# samd21_actuatorhub_Lite_TQFP32_1_0_feb20.net
KiCad netlist of a schematic drawn in EAGLE
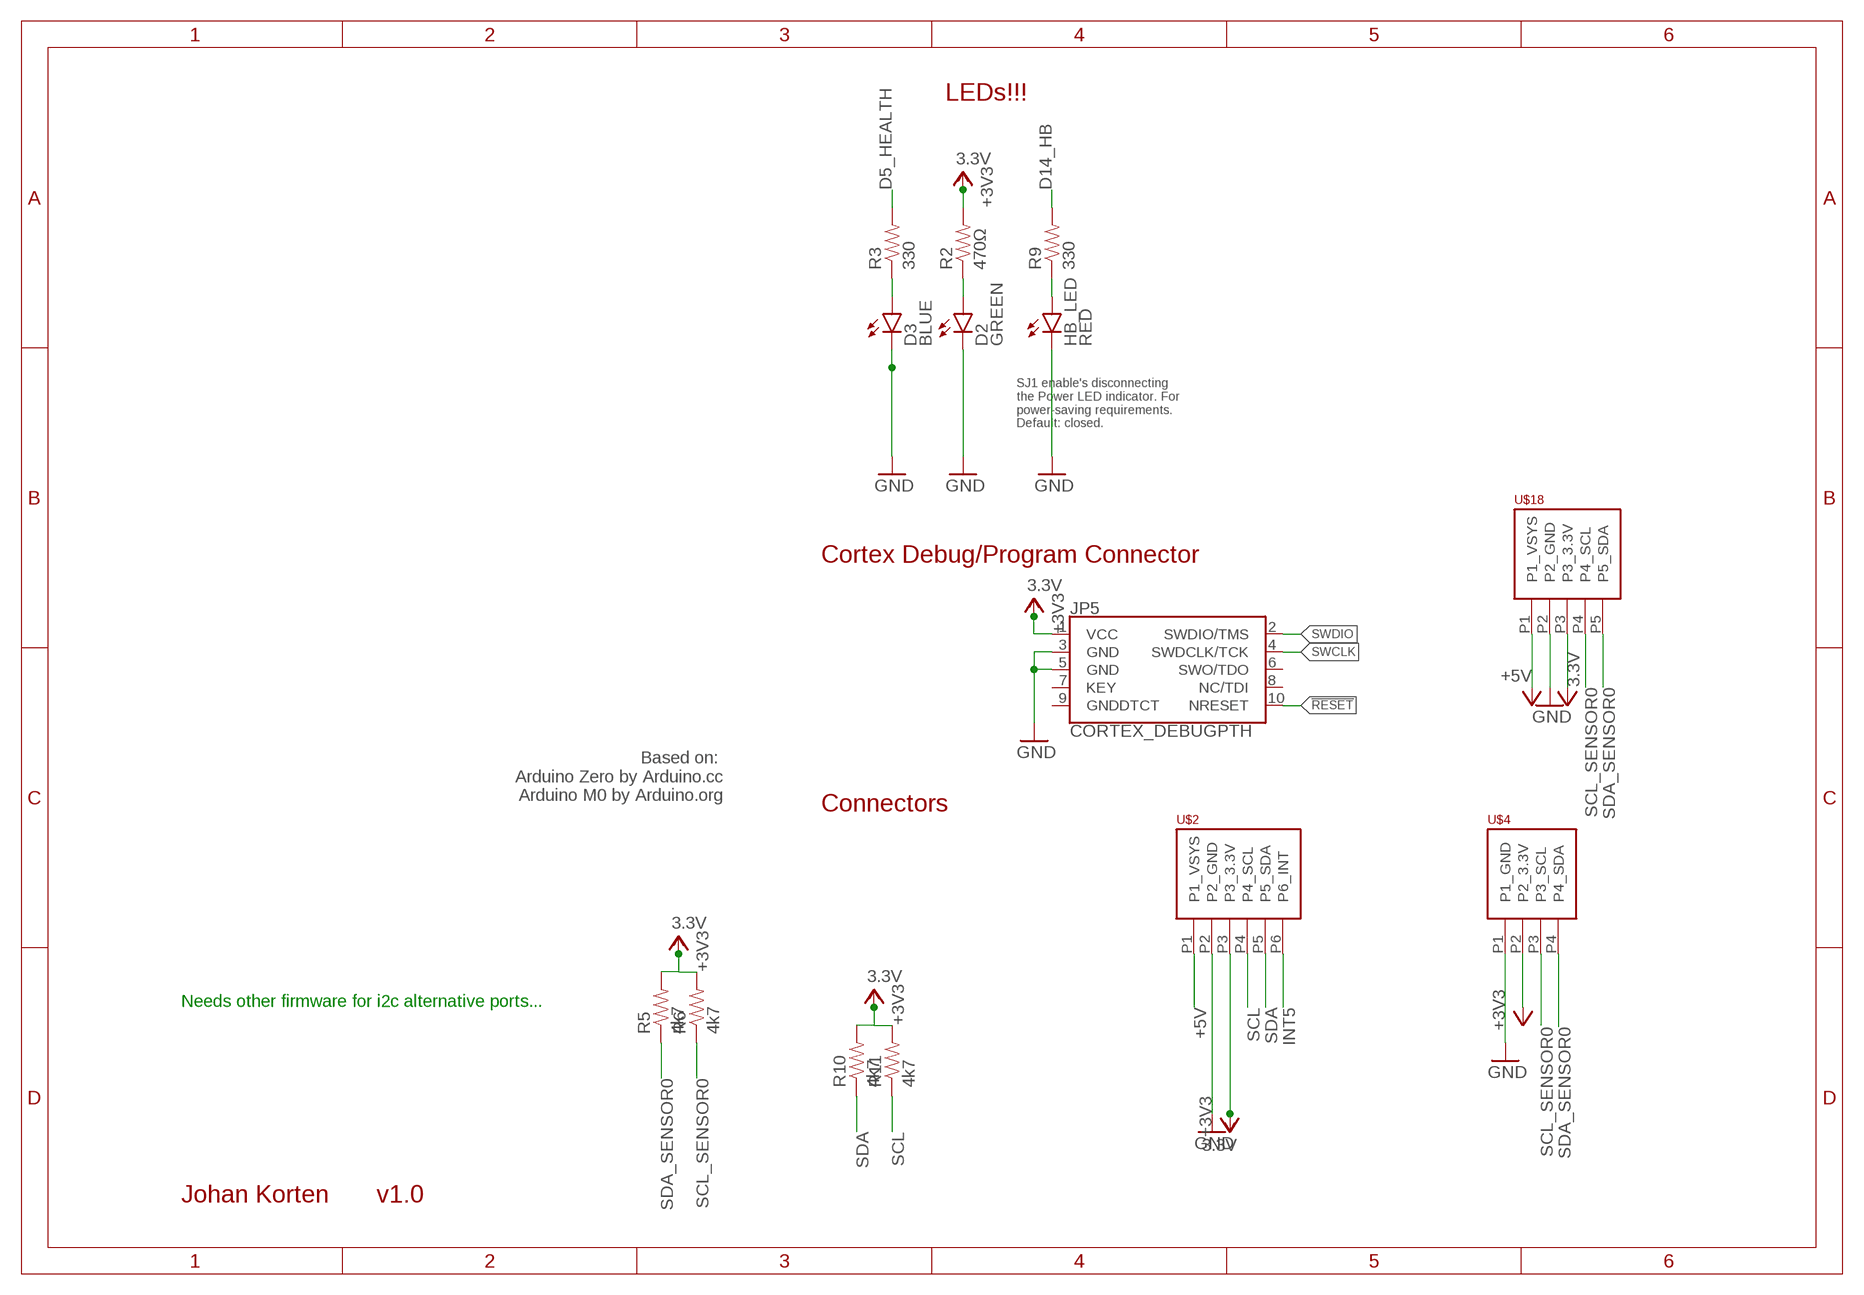
[diagram p0: schematic, sheet 1]
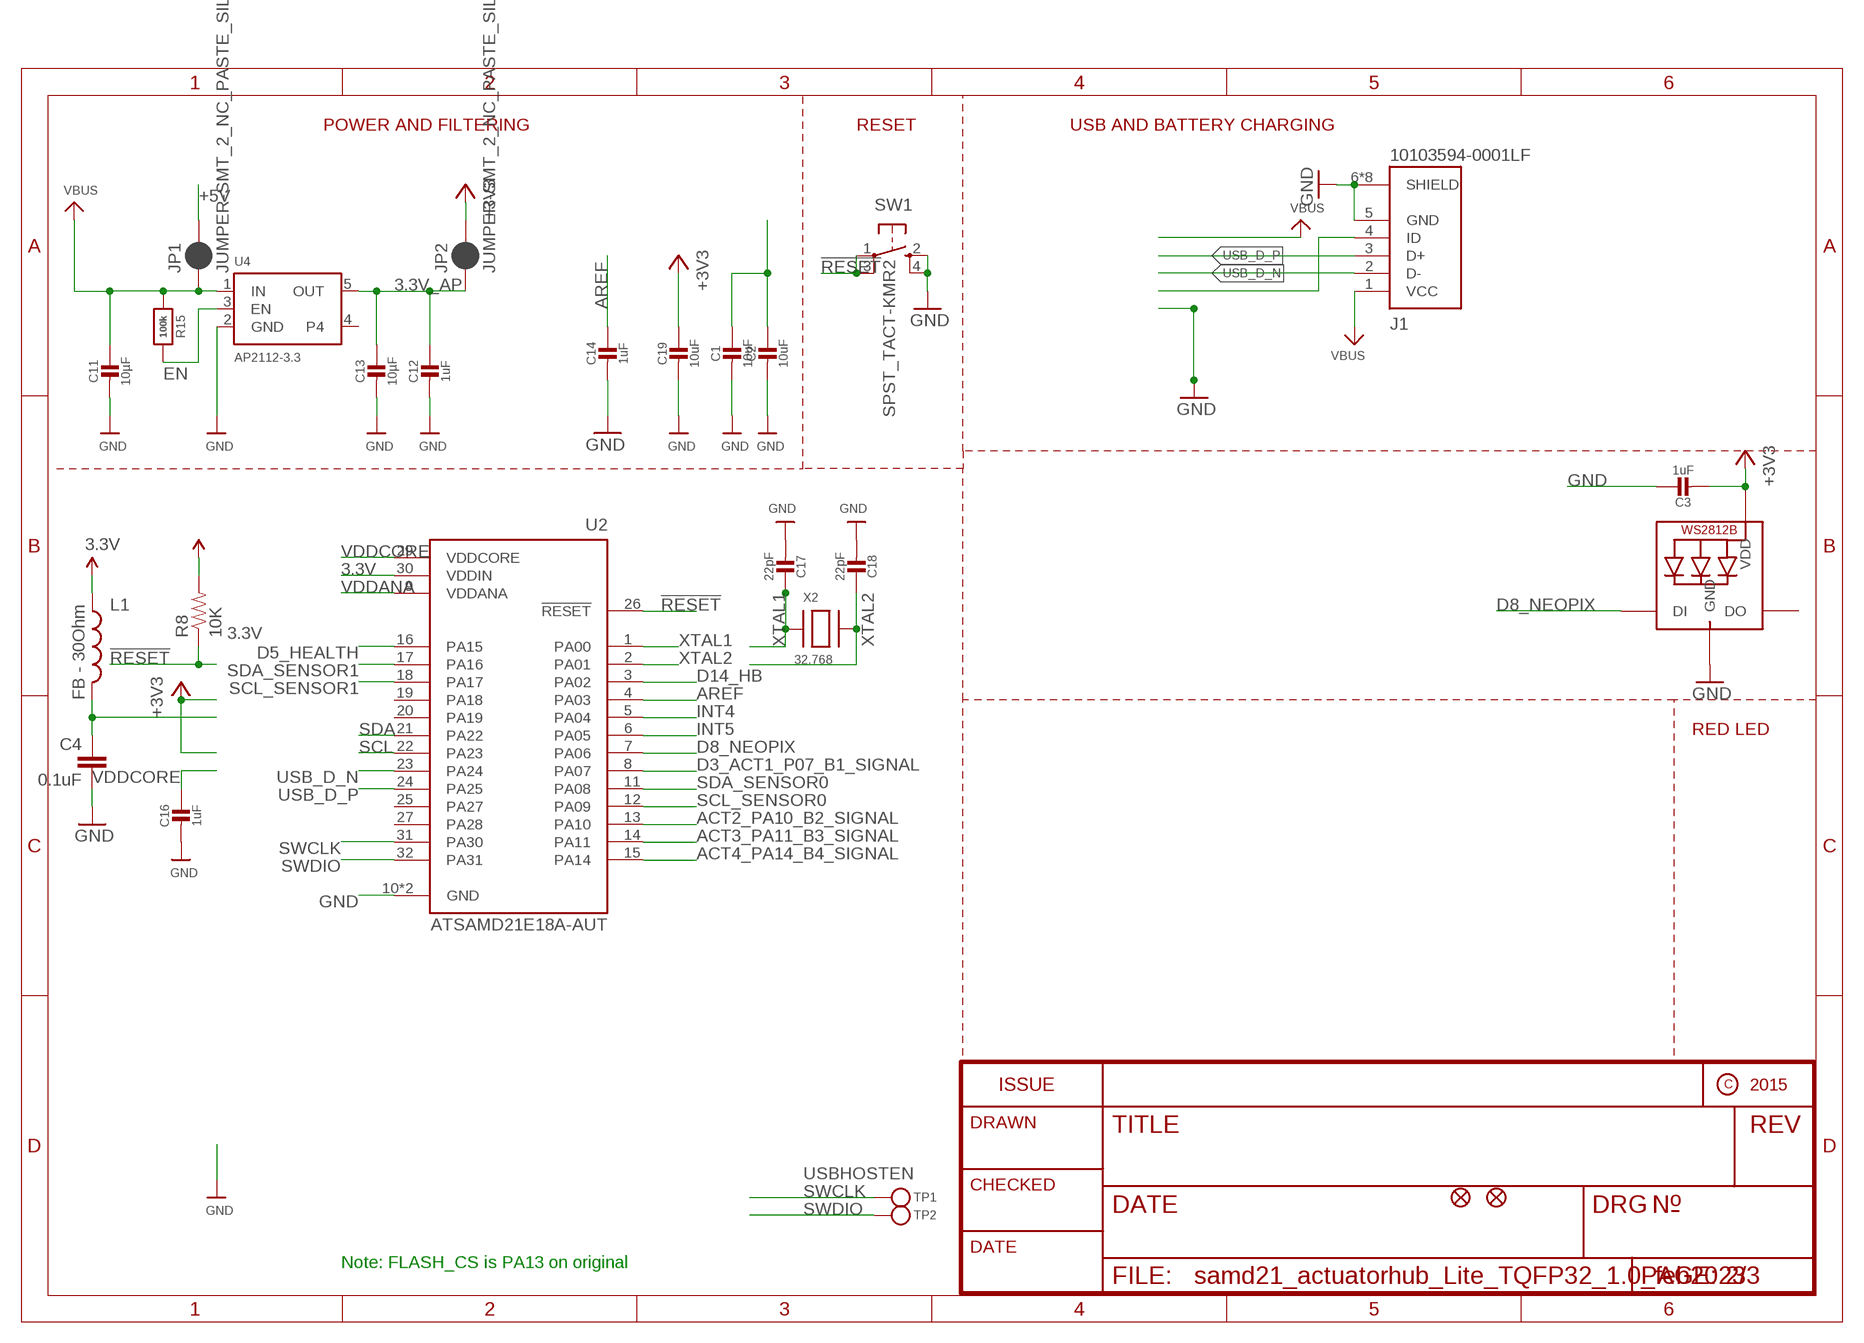
[diagram p1: schematic, sheet 2]
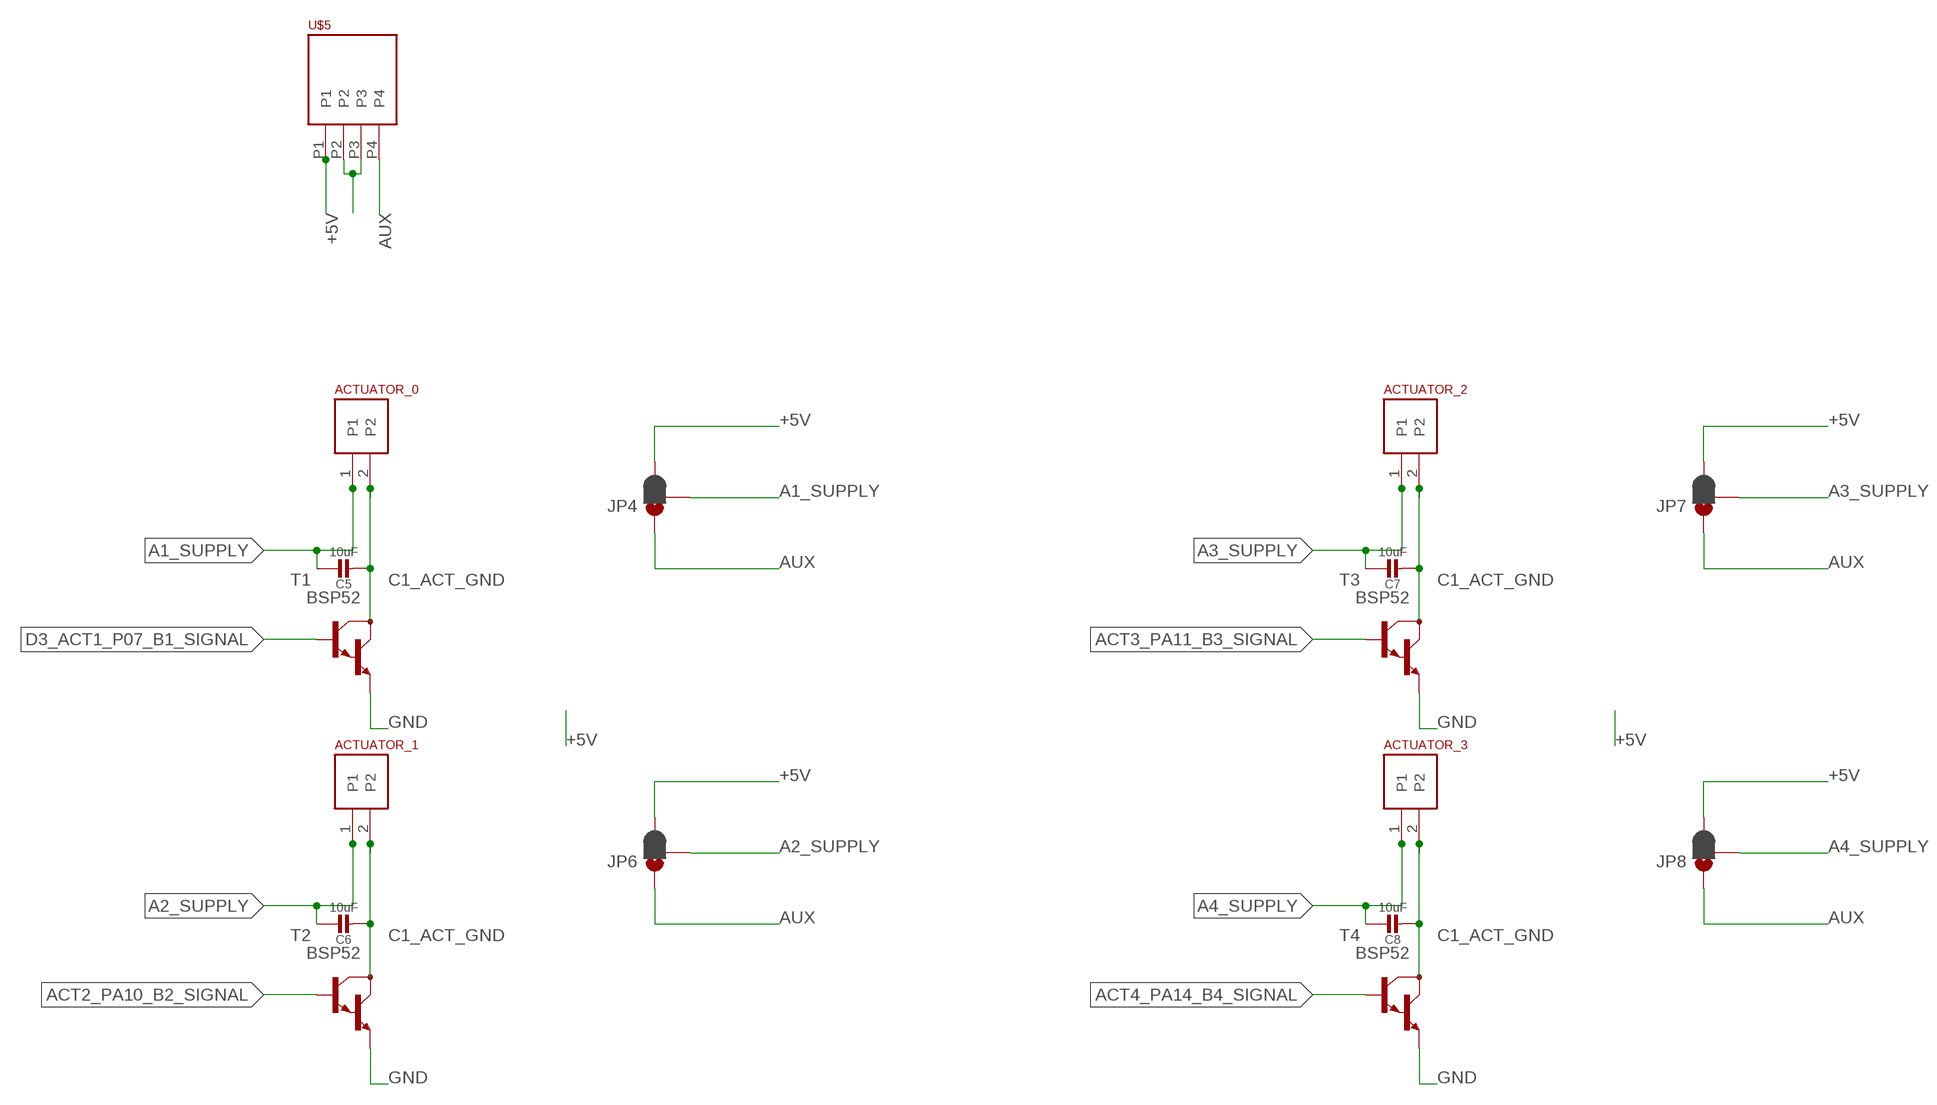
[diagram p2: schematic, sheet 3]

(export (version "E")
  (design (tool "Eeschema 10.0.6"))
  (components
    (comp (ref "ACTUATOR_0")
      (value "PHOENIX_PTSM_M2TH")
      (footprint "eagle-import:PTSM_M2_THRHOLE")
      (libsource (lib "eagle-import") (part "PHOENIX_PTSM_M2TH"))
    )
    (comp (ref "ACTUATOR_1")
      (value "PHOENIX_PTSM_M2TH")
      (footprint "eagle-import:PTSM_M2_THRHOLE")
      (libsource (lib "eagle-import") (part "PHOENIX_PTSM_M2TH"))
    )
    (comp (ref "ACTUATOR_2")
      (value "PHOENIX_PTSM_M2TH")
      (footprint "eagle-import:PTSM_M2_THRHOLE")
      (libsource (lib "eagle-import") (part "PHOENIX_PTSM_M2TH"))
    )
    (comp (ref "ACTUATOR_3")
      (value "PHOENIX_PTSM_M2TH")
      (footprint "eagle-import:PTSM_M2_THRHOLE")
      (libsource (lib "eagle-import") (part "PHOENIX_PTSM_M2TH"))
    )
    (comp (ref "C5")
      (value "10uF")
      (footprint "eagle-import:0805-NO")
      (libsource (lib "eagle-import") (part "CAP_CERAMIC0805-NOOUTLINE"))
    )
    (comp (ref "C6")
      (value "10uF")
      (footprint "eagle-import:0805-NO")
      (libsource (lib "eagle-import") (part "CAP_CERAMIC0805-NOOUTLINE"))
    )
    (comp (ref "C7")
      (value "10uF")
      (footprint "eagle-import:0805-NO")
      (libsource (lib "eagle-import") (part "CAP_CERAMIC0805-NOOUTLINE"))
    )
    (comp (ref "C8")
      (value "10uF")
      (footprint "eagle-import:0805-NO")
      (libsource (lib "eagle-import") (part "CAP_CERAMIC0805-NOOUTLINE"))
    )
    (comp (ref "JP4")
      (value "JUMPER-SMT_3_1-NC_PASTE_SILK")
      (footprint "eagle-import:SMT-JUMPER_3_1-NC_PASTE_SILK")
      (libsource (lib "eagle-import") (part "JUMPER-SMT_3_1-NC_PASTE_SILK"))
    )
    (comp (ref "JP6")
      (value "JUMPER-SMT_3_1-NC_PASTE_SILK")
      (footprint "eagle-import:SMT-JUMPER_3_1-NC_PASTE_SILK")
      (libsource (lib "eagle-import") (part "JUMPER-SMT_3_1-NC_PASTE_SILK"))
    )
    (comp (ref "JP7")
      (value "JUMPER-SMT_3_1-NC_PASTE_SILK")
      (footprint "eagle-import:SMT-JUMPER_3_1-NC_PASTE_SILK")
      (libsource (lib "eagle-import") (part "JUMPER-SMT_3_1-NC_PASTE_SILK"))
    )
    (comp (ref "JP8")
      (value "JUMPER-SMT_3_1-NC_PASTE_SILK")
      (footprint "eagle-import:SMT-JUMPER_3_1-NC_PASTE_SILK")
      (libsource (lib "eagle-import") (part "JUMPER-SMT_3_1-NC_PASTE_SILK"))
    )
    (comp (ref "T1")
      (value "BSP52")
      (footprint "eagle-import:SOT-223-4")
      (fields (field (name "MF") "ON Semiconductor"))
      (libsource (lib "eagle-import") (part "BSP52"))
    )
    (comp (ref "T2")
      (value "BSP52")
      (footprint "eagle-import:SOT-223-4")
      (fields (field (name "MF") "ON Semiconductor"))
      (libsource (lib "eagle-import") (part "BSP52"))
    )
    (comp (ref "T3")
      (value "BSP52")
      (footprint "eagle-import:SOT-223-4")
      (fields (field (name "MF") "ON Semiconductor"))
      (libsource (lib "eagle-import") (part "BSP52"))
    )
    (comp (ref "T4")
      (value "BSP52")
      (footprint "eagle-import:SOT-223-4")
      (fields (field (name "MF") "ON Semiconductor"))
      (libsource (lib "eagle-import") (part "BSP52"))
    )
    (comp (ref "U$5")
      (value "PHOENIX_PTSM_M4_TH_ANGLE")
      (footprint "eagle-import:PTSM_M4_TH_ANGLE_NEUTRAL")
      (libsource (lib "eagle-import") (part "PHOENIX_PTSM_M4_TH_ANGLE"))
    )
    (comp (ref "C1")
      (value "10uF")
      (footprint "eagle-import:0805-NO")
      (libsource (lib "eagle-import") (part "CAP_CERAMIC0805-NOOUTLINE"))
    )
    (comp (ref "C2")
      (value "10uF")
      (footprint "eagle-import:0805-NO")
      (libsource (lib "eagle-import") (part "CAP_CERAMIC0805-NOOUTLINE"))
    )
    (comp (ref "C3")
      (value "1uF")
      (footprint "eagle-import:0603-NO")
      (libsource (lib "eagle-import") (part "CAP_CERAMIC0603_NO"))
    )
    (comp (ref "C4")
      (value "0.1uF")
      (footprint "eagle-import:0402-CAP")
      (libsource (lib "eagle-import") (part "0.1UF-16V(+-10%)(0402)"))
    )
    (comp (ref "C11")
      (value "10µF")
      (footprint "eagle-import:0805-NO")
      (libsource (lib "eagle-import") (part "CAP_CERAMIC0805-NOOUTLINE"))
    )
    (comp (ref "C12")
      (value "1uF")
      (footprint "eagle-import:0603-NO")
      (libsource (lib "eagle-import") (part "CAP_CERAMIC0603_NO"))
    )
    (comp (ref "C13")
      (value "10µF")
      (footprint "eagle-import:0805-NO")
      (libsource (lib "eagle-import") (part "CAP_CERAMIC0805-NOOUTLINE"))
    )
    (comp (ref "C14")
      (value "1uF")
      (footprint "eagle-import:0603-NO")
      (libsource (lib "eagle-import") (part "CAP_CERAMIC0603_NO"))
    )
    (comp (ref "C16")
      (value "1uF")
      (footprint "eagle-import:0603-NO")
      (libsource (lib "eagle-import") (part "CAP_CERAMIC0603_NO"))
    )
    (comp (ref "C17")
      (value "22pF")
      (footprint "eagle-import:0603-NO")
      (libsource (lib "eagle-import") (part "CAP_CERAMIC0603_NO"))
    )
    (comp (ref "C18")
      (value "22pF")
      (footprint "eagle-import:0603-NO")
      (libsource (lib "eagle-import") (part "CAP_CERAMIC0603_NO"))
    )
    (comp (ref "C19")
      (value "10uF")
      (footprint "eagle-import:0805-NO")
      (libsource (lib "eagle-import") (part "CAP_CERAMIC0805-NOOUTLINE"))
    )
    (comp (ref "J1")
      (value "10103594-0001LF")
      (footprint "eagle-import:AMPHENOL_10103594-0001LF")
      (fields (field (name "MF") "AMPHENOL ICC / FCI"))
      (libsource (lib "eagle-import") (part "10103594-0001LF"))
    )
    (comp (ref "JP1")
      (value "JUMPER-SMT_2_NC_PASTE_SILK")
      (footprint "eagle-import:SMT-JUMPER_2_NC_PASTE_SILK")
      (libsource (lib "eagle-import") (part "JUMPER-SMT_2_NC_PASTE_SILK"))
    )
    (comp (ref "JP2")
      (value "JUMPER-SMT_2_NC_PASTE_SILK")
      (footprint "eagle-import:SMT-JUMPER_2_NC_PASTE_SILK")
      (libsource (lib "eagle-import") (part "JUMPER-SMT_2_NC_PASTE_SILK"))
    )
    (comp (ref "L1")
      (value "FB - 30Ohm")
      (footprint "eagle-import:0603")
      (libsource (lib "eagle-import") (part "INDUCTOR0603"))
    )
    (comp (ref "LED1")
      (value "WS2812B3535")
      (footprint "eagle-import:LED3535")
      (libsource (lib "eagle-import") (part "WS2812B3535"))
    )
    (comp (ref "R8")
      (value "10K")
      (footprint "eagle-import:0603-RES")
      (libsource (lib "eagle-import") (part "10KOHM-1/10W-1%(0603)0603"))
    )
    (comp (ref "R15")
      (value "100k")
      (footprint "eagle-import:0603-NO")
      (libsource (lib "eagle-import") (part "RESISTOR_0603_NOOUT"))
    )
    (comp (ref "SW1")
      (value "SPST_TACT-KMR2")
      (footprint "eagle-import:KMR2")
      (libsource (lib "eagle-import") (part "SPST_TACT-KMR2"))
    )
    (comp (ref "TP1")
      (value "TESTPOINTROUND1.5MM")
      (footprint "eagle-import:TESTPOINT_ROUND_1.5MM")
      (libsource (lib "eagle-import") (part "TESTPOINTROUND1.5MM"))
    )
    (comp (ref "TP2")
      (value "TESTPOINTROUND1.5MM")
      (footprint "eagle-import:TESTPOINT_ROUND_1.5MM")
      (libsource (lib "eagle-import") (part "TESTPOINTROUND1.5MM"))
    )
    (comp (ref "U$34")
      (value "FIDUCIAL\"\"")
      (footprint "eagle-import:FIDUCIAL_1MM")
      (libsource (lib "eagle-import") (part "FIDUCIAL{dblquote}{dblquote}"))
    )
    (comp (ref "U$35")
      (value "FIDUCIAL\"\"")
      (footprint "eagle-import:FIDUCIAL_1MM")
      (libsource (lib "eagle-import") (part "FIDUCIAL{dblquote}{dblquote}"))
    )
    (comp (ref "U2")
      (value "ATSAMD21E18A-AUT")
      (footprint "eagle-import:QFP80P900X900X120-32N")
      (fields (field (name "MF") "Microchip") (field (name "MP") "ATSAMD21E18A-AU"))
      (libsource (lib "eagle-import") (part "ATSAMD21E18A-AUT"))
    )
    (comp (ref "U4")
      (value "AP2112-3.3")
      (footprint "eagle-import:SOT23-5")
      (libsource (lib "eagle-import") (part "VREG_SOT23-5"))
    )
    (comp (ref "X2")
      (value "32.768")
      (footprint "eagle-import:XTAL3215")
      (libsource (lib "eagle-import") (part "XTAL-3.2X1.5"))
    )
    (comp (ref "D2")
      (value "GREEN")
      (footprint "eagle-import:LED-0603")
      (libsource (lib "eagle-import") (part "LED-RED0603"))
    )
    (comp (ref "D3")
      (value "BLUE")
      (footprint "eagle-import:LED-0603")
      (libsource (lib "eagle-import") (part "LED-BLUE0603"))
    )
    (comp (ref "HB_LED")
      (value "RED")
      (footprint "eagle-import:LED-0603")
      (libsource (lib "eagle-import") (part "LED-RED0603"))
    )
    (comp (ref "JP5")
      (value "CORTEX_DEBUGPTH")
      (footprint "eagle-import:2X5-PTH-1.27MM")
      (libsource (lib "eagle-import") (part "CORTEX_DEBUGPTH"))
    )
    (comp (ref "R2")
      (value "470Ω")
      (footprint "eagle-import:0603-RES")
      (libsource (lib "eagle-import") (part "330OHM1/10W1%(0603)"))
    )
    (comp (ref "R3")
      (value "330")
      (footprint "eagle-import:0603-RES")
      (libsource (lib "eagle-import") (part "330OHM1/10W1%(0603)"))
    )
    (comp (ref "R5")
      (value "4k7")
      (footprint "eagle-import:0603-RES")
      (libsource (lib "eagle-import") (part "330OHM1/10W1%(0603)"))
    )
    (comp (ref "R6")
      (value "4k7")
      (footprint "eagle-import:0603-RES")
      (libsource (lib "eagle-import") (part "330OHM1/10W1%(0603)"))
    )
    (comp (ref "R9")
      (value "330")
      (footprint "eagle-import:0603-RES")
      (libsource (lib "eagle-import") (part "330OHM1/10W1%(0603)"))
    )
    (comp (ref "R10")
      (value "4k7")
      (footprint "eagle-import:0603-RES")
      (libsource (lib "eagle-import") (part "330OHM1/10W1%(0603)"))
    )
    (comp (ref "R11")
      (value "4k7")
      (footprint "eagle-import:0603-RES")
      (libsource (lib "eagle-import") (part "330OHM1/10W1%(0603)"))
    )
    (comp (ref "U$2")
      (value "PHOENIX_PTSM_M6_TH_I2CPPANGLE")
      (footprint "eagle-import:PTSM_M6_THRHOLE")
      (libsource (lib "eagle-import") (part "PHOENIX_PTSM_M6_TH_I2CPPANGLE"))
    )
    (comp (ref "U$4")
      (value "PHOENIX_PTSM_M4_THANGLE")
      (footprint "eagle-import:PTSM_M4_TH")
      (libsource (lib "eagle-import") (part "PHOENIX_PTSM_M4_THANGLE"))
    )
    (comp (ref "U$18")
      (value "PHOENIX_PTSM_M5_TH_I2C++")
      (footprint "eagle-import:PTSM_M5_THRHOLE")
      (libsource (lib "eagle-import") (part "PHOENIX_PTSM_M5_TH_I2C++"))
    )
  )
  (nets
    (net (code "1") (name "+5V") (class "Default")
      (node (ref "C1") (pin "1") (pinfunction "1_1") (pintype "passive"))
      (node (ref "C2") (pin "1") (pinfunction "1_1") (pintype "passive"))
      (node (ref "JP1") (pin "2") (pinfunction "2_2") (pintype "passive"))
      (node (ref "JP4") (pin "3") (pinfunction "3_3") (pintype "passive"))
      (node (ref "JP6") (pin "3") (pinfunction "3_3") (pintype "passive"))
      (node (ref "JP7") (pin "3") (pinfunction "3_3") (pintype "passive"))
      (node (ref "JP8") (pin "3") (pinfunction "3_3") (pintype "passive"))
      (node (ref "U$18") (pin "P1") (pinfunction "P1_VSYS_P1") (pintype "power_in"))
      (node (ref "U$2") (pin "P1") (pinfunction "P1_VSYS_P1") (pintype "power_in"))
      (node (ref "U$5") (pin "P1") (pinfunction "P1_P1") (pintype "power_in"))
    )
    (net (code "2") (name "3.3V") (class "Default")
      (node (ref "C19") (pin "1") (pinfunction "1_1") (pintype "passive"))
      (node (ref "C3") (pin "2") (pinfunction "2_2") (pintype "passive"))
      (node (ref "JP2") (pin "2") (pinfunction "2_2") (pintype "passive"))
      (node (ref "JP5") (pin "1") (pinfunction "VCC_1") (pintype "bidirectional"))
      (node (ref "L1") (pin "1") (pinfunction "1_1") (pintype "passive"))
      (node (ref "LED1") (pin "2") (pinfunction "VDD_2") (pintype "power_in"))
      (node (ref "R10") (pin "2") (pinfunction "2_2") (pintype "passive"))
      (node (ref "R11") (pin "2") (pinfunction "2_2") (pintype "passive"))
      (node (ref "R2") (pin "2") (pinfunction "2_2") (pintype "passive"))
      (node (ref "R5") (pin "2") (pinfunction "2_2") (pintype "passive"))
      (node (ref "R6") (pin "2") (pinfunction "2_2") (pintype "passive"))
      (node (ref "R8") (pin "2") (pinfunction "2_2") (pintype "passive"))
      (node (ref "U$18") (pin "P3") (pinfunction "P3_3.3V_P3") (pintype "power_in"))
      (node (ref "U$2") (pin "P3") (pinfunction "P3_3.3V_P3") (pintype "power_in"))
      (node (ref "U$4") (pin "P2") (pinfunction "P2_3.3V_P2") (pintype "power_in"))
      (node (ref "U2") (pin "30") (pinfunction "VDDIN_30") (pintype "power_in"))
    )
    (net (code "3") (name "3.3V_AP") (class "Default")
      (node (ref "C12") (pin "1") (pinfunction "1_1") (pintype "passive"))
      (node (ref "C13") (pin "1") (pinfunction "1_1") (pintype "passive"))
      (node (ref "JP2") (pin "1") (pinfunction "1_1") (pintype "passive"))
      (node (ref "U4") (pin "5") (pinfunction "OUT_5") (pintype "power_in"))
    )
    (net (code "4") (name "A1_SUPPLY") (class "Default")
      (node (ref "ACTUATOR_0") (pin "1") (pinfunction "P1_1") (pintype "bidirectional"))
      (node (ref "C5") (pin "1") (pinfunction "1_1") (pintype "passive"))
      (node (ref "JP4") (pin "2") (pinfunction "2_2") (pintype "passive"))
    )
    (net (code "5") (name "A2_SUPPLY") (class "Default")
      (node (ref "ACTUATOR_1") (pin "1") (pinfunction "P1_1") (pintype "bidirectional"))
      (node (ref "C6") (pin "1") (pinfunction "1_1") (pintype "passive"))
      (node (ref "JP6") (pin "2") (pinfunction "2_2") (pintype "passive"))
    )
    (net (code "6") (name "A3_SUPPLY") (class "Default")
      (node (ref "ACTUATOR_2") (pin "1") (pinfunction "P1_1") (pintype "bidirectional"))
      (node (ref "C7") (pin "1") (pinfunction "1_1") (pintype "passive"))
      (node (ref "JP7") (pin "2") (pinfunction "2_2") (pintype "passive"))
    )
    (net (code "7") (name "A4_SUPPLY") (class "Default")
      (node (ref "ACTUATOR_3") (pin "1") (pinfunction "P1_1") (pintype "bidirectional"))
      (node (ref "C8") (pin "1") (pinfunction "1_1") (pintype "passive"))
      (node (ref "JP8") (pin "2") (pinfunction "2_2") (pintype "passive"))
    )
    (net (code "8") (name "ACT2_PA10_B2_SIGNAL") (class "Default")
      (node (ref "T2") (pin "1") (pinfunction "B_1") (pintype "passive"))
      (node (ref "U2") (pin "13") (pinfunction "PA10_13") (pintype "bidirectional"))
    )
    (net (code "9") (name "ACT3_PA11_B3_SIGNAL") (class "Default")
      (node (ref "T3") (pin "1") (pinfunction "B_1") (pintype "passive"))
      (node (ref "U2") (pin "14") (pinfunction "PA11_14") (pintype "bidirectional"))
    )
    (net (code "10") (name "ACT4_PA14_B4_SIGNAL") (class "Default")
      (node (ref "T4") (pin "1") (pinfunction "B_1") (pintype "passive"))
      (node (ref "U2") (pin "15") (pinfunction "PA14_15") (pintype "bidirectional"))
    )
    (net (code "11") (name "AREF") (class "Default")
      (node (ref "C14") (pin "1") (pinfunction "1_1") (pintype "passive"))
      (node (ref "U2") (pin "4") (pinfunction "PA03_4") (pintype "bidirectional"))
    )
    (net (code "12") (name "AUX") (class "Default")
      (node (ref "JP4") (pin "1") (pinfunction "1_1") (pintype "passive"))
      (node (ref "JP6") (pin "1") (pinfunction "1_1") (pintype "passive"))
      (node (ref "JP7") (pin "1") (pinfunction "1_1") (pintype "passive"))
      (node (ref "JP8") (pin "1") (pinfunction "1_1") (pintype "passive"))
      (node (ref "U$5") (pin "P4") (pinfunction "P4_P4") (pintype "power_in"))
    )
    (net (code "13") (name "C1_ACT_GND") (class "Default")
      (node (ref "ACTUATOR_0") (pin "2") (pinfunction "P2_2") (pintype "bidirectional"))
      (node (ref "ACTUATOR_1") (pin "2") (pinfunction "P2_2") (pintype "bidirectional"))
      (node (ref "ACTUATOR_2") (pin "2") (pinfunction "P2_2") (pintype "bidirectional"))
      (node (ref "ACTUATOR_3") (pin "2") (pinfunction "P2_2") (pintype "bidirectional"))
      (node (ref "C5") (pin "2") (pinfunction "2_2") (pintype "passive"))
      (node (ref "C6") (pin "2") (pinfunction "2_2") (pintype "passive"))
      (node (ref "C7") (pin "2") (pinfunction "2_2") (pintype "passive"))
      (node (ref "C8") (pin "2") (pinfunction "2_2") (pintype "passive"))
      (node (ref "T1") (pin "2") (pinfunction "C_2") (pintype "passive"))
      (node (ref "T1") (pin "4") (pinfunction "C_4") (pintype "passive"))
      (node (ref "T2") (pin "2") (pinfunction "C_2") (pintype "passive"))
      (node (ref "T2") (pin "4") (pinfunction "C_4") (pintype "passive"))
      (node (ref "T3") (pin "2") (pinfunction "C_2") (pintype "passive"))
      (node (ref "T3") (pin "4") (pinfunction "C_4") (pintype "passive"))
      (node (ref "T4") (pin "2") (pinfunction "C_2") (pintype "passive"))
      (node (ref "T4") (pin "4") (pinfunction "C_4") (pintype "passive"))
    )
    (net (code "14") (name "D3_ACT1_P07_B1_SIGNAL") (class "Default")
      (node (ref "T1") (pin "1") (pinfunction "B_1") (pintype "passive"))
      (node (ref "U2") (pin "8") (pinfunction "PA07_8") (pintype "bidirectional"))
    )
    (net (code "15") (name "D5_HEALTH") (class "Default")
      (node (ref "R3") (pin "2") (pinfunction "2_2") (pintype "passive"))
      (node (ref "U2") (pin "16") (pinfunction "PA15_16") (pintype "bidirectional"))
    )
    (net (code "16") (name "D8_NEOPIX") (class "Default")
      (node (ref "LED1") (pin "1") (pinfunction "DI_1") (pintype "input"))
      (node (ref "U2") (pin "7") (pinfunction "PA06_7") (pintype "bidirectional"))
    )
    (net (code "17") (name "D14_HB") (class "Default")
      (node (ref "R9") (pin "2") (pinfunction "2_2") (pintype "passive"))
      (node (ref "U2") (pin "3") (pinfunction "PA02_3") (pintype "bidirectional"))
    )
    (net (code "18") (name "EN") (class "Default")
      (node (ref "R15") (pin "2") (pinfunction "2_2") (pintype "passive"))
      (node (ref "U4") (pin "3") (pinfunction "EN_3") (pintype "input"))
    )
    (net (code "19") (name "GND") (class "Default")
      (node (ref "C1") (pin "2") (pinfunction "2_2") (pintype "passive"))
      (node (ref "C11") (pin "2") (pinfunction "2_2") (pintype "passive"))
      (node (ref "C12") (pin "2") (pinfunction "2_2") (pintype "passive"))
      (node (ref "C13") (pin "2") (pinfunction "2_2") (pintype "passive"))
      (node (ref "C14") (pin "2") (pinfunction "2_2") (pintype "passive"))
      (node (ref "C16") (pin "2") (pinfunction "2_2") (pintype "passive"))
      (node (ref "C17") (pin "2") (pinfunction "2_2") (pintype "passive"))
      (node (ref "C18") (pin "2") (pinfunction "2_2") (pintype "passive"))
      (node (ref "C19") (pin "2") (pinfunction "2_2") (pintype "passive"))
      (node (ref "C2") (pin "2") (pinfunction "2_2") (pintype "passive"))
      (node (ref "C3") (pin "1") (pinfunction "1_1") (pintype "passive"))
      (node (ref "C4") (pin "2") (pinfunction "2_2") (pintype "passive"))
      (node (ref "D2") (pin "C") (pinfunction "C_C") (pintype "passive"))
      (node (ref "D3") (pin "C") (pinfunction "C_C") (pintype "passive"))
      (node (ref "HB_LED") (pin "C") (pinfunction "C_C") (pintype "passive"))
      (node (ref "J1") (pin "10") (pinfunction "SHIELD_10") (pintype "passive"))
      (node (ref "J1") (pin "11") (pinfunction "SHIELD_11") (pintype "passive"))
      (node (ref "J1") (pin "5") (pinfunction "GND_5") (pintype "power_in"))
      (node (ref "J1") (pin "6") (pinfunction "SHIELD_6") (pintype "passive"))
      (node (ref "J1") (pin "7") (pinfunction "SHIELD_7") (pintype "passive"))
      (node (ref "J1") (pin "8") (pinfunction "SHIELD_8") (pintype "passive"))
      (node (ref "J1") (pin "9") (pinfunction "SHIELD_9") (pintype "passive"))
      (node (ref "J1") (pin "S1") (pinfunction "SHIELD_S1") (pintype "passive"))
      (node (ref "J1") (pin "S2") (pinfunction "SHIELD_S2") (pintype "passive"))
      (node (ref "JP5") (pin "3") (pinfunction "GND_3") (pintype "bidirectional"))
      (node (ref "JP5") (pin "5") (pinfunction "GND_5") (pintype "bidirectional"))
      (node (ref "LED1") (pin "4") (pinfunction "GND_4") (pintype "power_in"))
      (node (ref "SW1") (pin "2") (pinfunction "S_2") (pintype "passive"))
      (node (ref "SW1") (pin "4") (pinfunction "S1_4") (pintype "passive"))
      (node (ref "T1") (pin "3") (pinfunction "E_3") (pintype "passive"))
      (node (ref "T2") (pin "3") (pinfunction "E_3") (pintype "passive"))
      (node (ref "T3") (pin "3") (pinfunction "E_3") (pintype "passive"))
      (node (ref "T4") (pin "3") (pinfunction "E_3") (pintype "passive"))
      (node (ref "U$18") (pin "P2") (pinfunction "P2_GND_P2") (pintype "power_in"))
      (node (ref "U$2") (pin "P2") (pinfunction "P2_GND_P2") (pintype "power_in"))
      (node (ref "U$4") (pin "P1") (pinfunction "P1_GND_P1") (pintype "power_in"))
      (node (ref "U2") (pin "10") (pinfunction "GND_10") (pintype "power_in"))
      (node (ref "U2") (pin "28") (pinfunction "GND_28") (pintype "power_in"))
      (node (ref "U4") (pin "2") (pinfunction "GND_2") (pintype "power_in"))
    )
    (net (code "20") (name "INT4") (class "Default")
      (node (ref "U2") (pin "5") (pinfunction "PA04_5") (pintype "bidirectional"))
    )
    (net (code "21") (name "INT5") (class "Default")
      (node (ref "U$2") (pin "P6") (pinfunction "P6_INT_P6") (pintype "power_in"))
      (node (ref "U2") (pin "6") (pinfunction "PA05_6") (pintype "bidirectional"))
    )
    (net (code "22") (name "Net-(D2-PadA)") (class "Default")
      (node (ref "D2") (pin "A") (pinfunction "A_A") (pintype "passive"))
      (node (ref "R2") (pin "1") (pinfunction "1_1") (pintype "passive"))
    )
    (net (code "23") (name "Net-(D3-PadA)") (class "Default")
      (node (ref "D3") (pin "A") (pinfunction "A_A") (pintype "passive"))
      (node (ref "R3") (pin "1") (pinfunction "1_1") (pintype "passive"))
    )
    (net (code "24") (name "Net-(HB_LED-PadA)") (class "Default")
      (node (ref "HB_LED") (pin "A") (pinfunction "A_A") (pintype "passive"))
      (node (ref "R9") (pin "1") (pinfunction "1_1") (pintype "passive"))
    )
    (net (code "25") (name "Net-(U$5-PadP2)") (class "Default")
      (node (ref "U$5") (pin "P2") (pinfunction "P2_P2") (pintype "power_in"))
      (node (ref "U$5") (pin "P3") (pinfunction "P3_P3") (pintype "power_in"))
    )
    (net (code "26") (name "SCL") (class "Default")
      (node (ref "R11") (pin "1") (pinfunction "1_1") (pintype "passive"))
      (node (ref "U$2") (pin "P4") (pinfunction "P4_SCL_P4") (pintype "bidirectional"))
      (node (ref "U2") (pin "22") (pinfunction "PA23_22") (pintype "bidirectional"))
    )
    (net (code "27") (name "SCL_SENSOR0") (class "Default")
      (node (ref "R6") (pin "1") (pinfunction "1_1") (pintype "passive"))
      (node (ref "U$18") (pin "P4") (pinfunction "P4_SCL_P4") (pintype "bidirectional"))
      (node (ref "U$4") (pin "P3") (pinfunction "P3_SCL_P3") (pintype "bidirectional"))
      (node (ref "U2") (pin "12") (pinfunction "PA09_12") (pintype "bidirectional"))
    )
    (net (code "28") (name "SCL_SENSOR1") (class "Default")
      (node (ref "U2") (pin "18") (pinfunction "PA17_18") (pintype "bidirectional"))
    )
    (net (code "29") (name "SDA") (class "Default")
      (node (ref "R10") (pin "1") (pinfunction "1_1") (pintype "passive"))
      (node (ref "U$2") (pin "P5") (pinfunction "P5_SDA_P5") (pintype "bidirectional"))
      (node (ref "U2") (pin "21") (pinfunction "PA22_21") (pintype "bidirectional"))
    )
    (net (code "30") (name "SDA_SENSOR0") (class "Default")
      (node (ref "R5") (pin "1") (pinfunction "1_1") (pintype "passive"))
      (node (ref "U$18") (pin "P5") (pinfunction "P5_SDA_P5") (pintype "bidirectional"))
      (node (ref "U$4") (pin "P4") (pinfunction "P4_SDA_P4") (pintype "bidirectional"))
      (node (ref "U2") (pin "11") (pinfunction "PA08_11") (pintype "bidirectional"))
    )
    (net (code "31") (name "SDA_SENSOR1") (class "Default")
      (node (ref "U2") (pin "17") (pinfunction "PA16_17") (pintype "bidirectional"))
    )
    (net (code "32") (name "SWCLK") (class "Default")
      (node (ref "JP5") (pin "4") (pinfunction "SWDCLK/TCK_4") (pintype "bidirectional"))
      (node (ref "TP1") (pin "P$1") (pinfunction "P$1_P$1") (pintype "bidirectional"))
      (node (ref "U2") (pin "31") (pinfunction "PA30_31") (pintype "bidirectional"))
    )
    (net (code "33") (name "SWDIO") (class "Default")
      (node (ref "JP5") (pin "2") (pinfunction "SWDIO/TMS_2") (pintype "bidirectional"))
      (node (ref "TP2") (pin "P$1") (pinfunction "P$1_P$1") (pintype "bidirectional"))
      (node (ref "U2") (pin "32") (pinfunction "PA31_32") (pintype "bidirectional"))
    )
    (net (code "34") (name "USB_D_N") (class "Default")
      (node (ref "J1") (pin "2") (pinfunction "D-_2") (pintype "bidirectional"))
      (node (ref "U2") (pin "23") (pinfunction "PA24_23") (pintype "bidirectional"))
    )
    (net (code "35") (name "USB_D_P") (class "Default")
      (node (ref "J1") (pin "3") (pinfunction "D+_3") (pintype "bidirectional"))
      (node (ref "U2") (pin "24") (pinfunction "PA25_24") (pintype "bidirectional"))
    )
    (net (code "36") (name "VBUS") (class "Default")
      (node (ref "C11") (pin "1") (pinfunction "1_1") (pintype "passive"))
      (node (ref "J1") (pin "1") (pinfunction "VCC_1") (pintype "power_in"))
      (node (ref "JP1") (pin "1") (pinfunction "1_1") (pintype "passive"))
      (node (ref "R15") (pin "1") (pinfunction "1_1") (pintype "passive"))
      (node (ref "U4") (pin "1") (pinfunction "IN_1") (pintype "power_in"))
    )
    (net (code "37") (name "VDDANA") (class "Default")
      (node (ref "C4") (pin "1") (pinfunction "1_1") (pintype "passive"))
      (node (ref "L1") (pin "2") (pinfunction "2_2") (pintype "passive"))
      (node (ref "U2") (pin "9") (pinfunction "VDDANA_9") (pintype "power_in"))
    )
    (net (code "38") (name "VDDCORE") (class "Default")
      (node (ref "C16") (pin "1") (pinfunction "1_1") (pintype "passive"))
      (node (ref "U2") (pin "29") (pinfunction "VDDCORE_29") (pintype "power_in"))
    )
    (net (code "39") (name "XTAL1") (class "Default")
      (node (ref "C17") (pin "1") (pinfunction "1_1") (pintype "passive"))
      (node (ref "U2") (pin "1") (pinfunction "PA00_1") (pintype "bidirectional"))
      (node (ref "X2") (pin "P$1") (pinfunction "P$1_P$1") (pintype "bidirectional"))
    )
    (net (code "40") (name "XTAL2") (class "Default")
      (node (ref "C18") (pin "1") (pinfunction "1_1") (pintype "passive"))
      (node (ref "U2") (pin "2") (pinfunction "PA01_2") (pintype "bidirectional"))
      (node (ref "X2") (pin "P$2") (pinfunction "P$2_P$2") (pintype "bidirectional"))
    )
    (net (code "41") (name "unconnected-(J1-ID-Pad4)") (class "Default")
      (node (ref "J1") (pin "4") (pinfunction "ID_4") (pintype "bidirectional"))
    )
    (net (code "42") (name "unconnected-(JP5-GNDDTCT-Pad9)") (class "Default")
      (node (ref "JP5") (pin "9") (pinfunction "GNDDTCT_9") (pintype "bidirectional"))
    )
    (net (code "43") (name "unconnected-(JP5-KEY-Pad7)") (class "Default")
      (node (ref "JP5") (pin "7") (pinfunction "KEY_7") (pintype "bidirectional"))
    )
    (net (code "44") (name "unconnected-(JP5-NC{slash}TDI-Pad8)") (class "Default")
      (node (ref "JP5") (pin "8") (pinfunction "NC/TDI_8") (pintype "bidirectional"))
    )
    (net (code "45") (name "unconnected-(JP5-SWO{slash}TDO-Pad6)") (class "Default")
      (node (ref "JP5") (pin "6") (pinfunction "SWO/TDO_6") (pintype "bidirectional"))
    )
    (net (code "46") (name "unconnected-(LED1-DO-Pad3)") (class "Default")
      (node (ref "LED1") (pin "3") (pinfunction "DO_3") (pintype "output"))
    )
    (net (code "47") (name "unconnected-(U2-PA18-Pad19)") (class "Default")
      (node (ref "U2") (pin "19") (pinfunction "PA18_19") (pintype "bidirectional"))
    )
    (net (code "48") (name "unconnected-(U2-PA19-Pad20)") (class "Default")
      (node (ref "U2") (pin "20") (pinfunction "PA19_20") (pintype "bidirectional"))
    )
    (net (code "49") (name "unconnected-(U2-PA27-Pad25)") (class "Default")
      (node (ref "U2") (pin "25") (pinfunction "PA27_25") (pintype "bidirectional"))
    )
    (net (code "50") (name "unconnected-(U2-PA28-Pad27)") (class "Default")
      (node (ref "U2") (pin "27") (pinfunction "PA28_27") (pintype "bidirectional"))
    )
    (net (code "51") (name "unconnected-(U4-P4-Pad4)") (class "Default")
      (node (ref "U4") (pin "4") (pinfunction "P4_4") (pintype "bidirectional"))
    )
    (net (code "52") (name "~{RESET}") (class "Default")
      (node (ref "JP5") (pin "10") (pinfunction "NRESET_10") (pintype "bidirectional"))
      (node (ref "R8") (pin "1") (pinfunction "1_1") (pintype "passive"))
      (node (ref "SW1") (pin "1") (pinfunction "P_1") (pintype "passive"))
      (node (ref "SW1") (pin "3") (pinfunction "P1_3") (pintype "passive"))
      (node (ref "U2") (pin "26") (pinfunction "~{RESET}_26") (pintype "input"))
    )
  )
)
